# ledControlpcb-NodeMCU.net
KiCad netlist of a schematic drawn in EAGLE
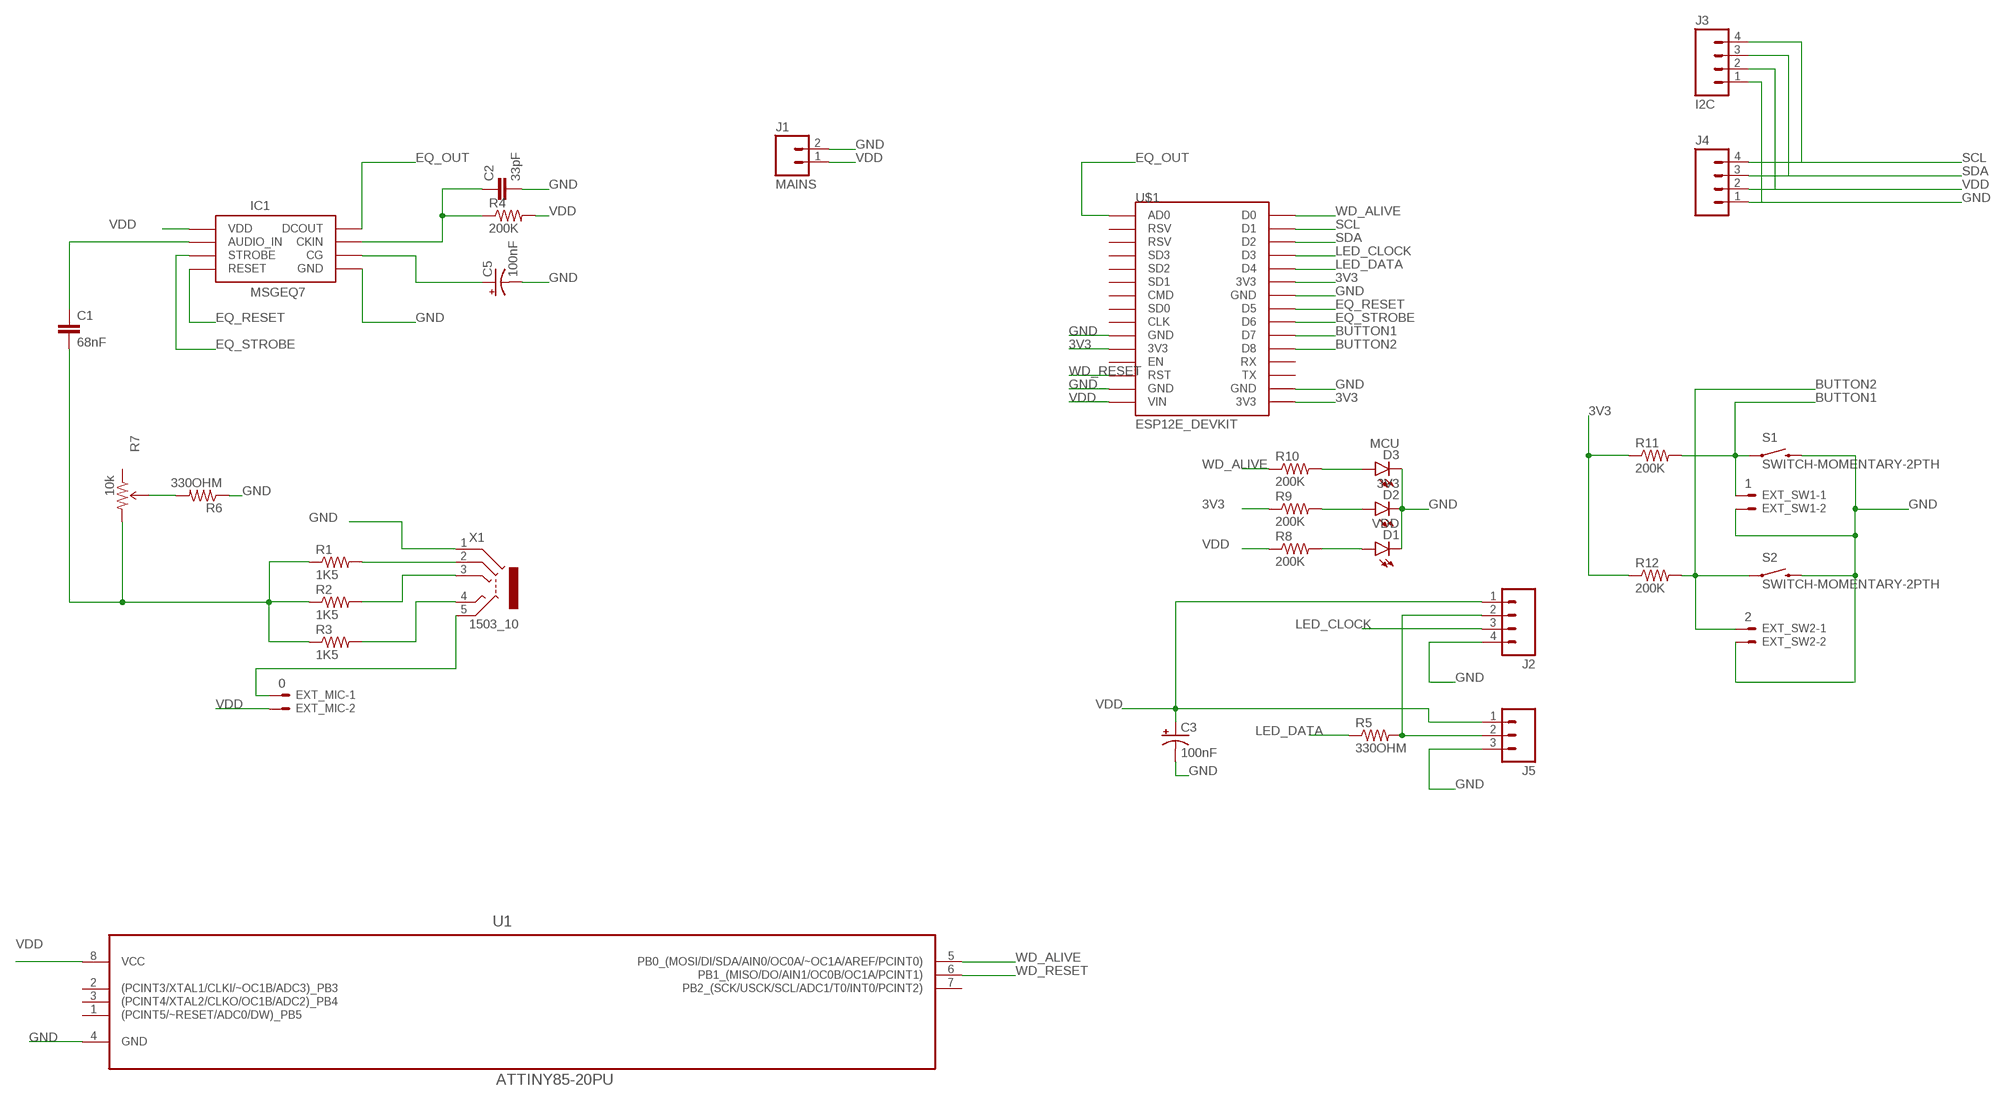
[diagram p0: schematic, sheet 1]

(export (version "E")
  (design (tool "Eeschema 10.0.6"))
  (components
    (comp (ref "C1")
      (value "68nF")
      (footprint "eagle-import:0603-CAP")
      (libsource (lib "eagle-import") (part "CAP0603-CAP"))
    )
    (comp (ref "C2")
      (value "33pF")
      (footprint "eagle-import:0603-CAP")
      (libsource (lib "eagle-import") (part "CAP0603-CAP"))
    )
    (comp (ref "C3")
      (value "100nF")
      (footprint "eagle-import:EIA3216")
      (libsource (lib "eagle-import") (part "CAP_POL1206"))
    )
    (comp (ref "C5")
      (value "100nF")
      (footprint "eagle-import:EIA3216")
      (libsource (lib "eagle-import") (part "CAP_POL1206"))
    )
    (comp (ref "D1")
      (value "VDD")
      (footprint "eagle-import:LED-0603")
      (libsource (lib "eagle-import") (part "LED0603"))
    )
    (comp (ref "D2")
      (value "3V3")
      (footprint "eagle-import:LED-0603")
      (libsource (lib "eagle-import") (part "LED0603"))
    )
    (comp (ref "D3")
      (value "MCU")
      (footprint "eagle-import:LED-0603")
      (libsource (lib "eagle-import") (part "LED0603"))
    )
    (comp (ref "EXT_MIC")
      (value "0")
      (footprint "eagle-import:22-23-2021")
      (fields (field (name "MF") "MOLEX") (field (name "MPN") "22-23-2021"))
      (libsource (lib "eagle-import") (part "22-23-2021"))
    )
    (comp (ref "EXT_SW1")
      (value "1")
      (footprint "eagle-import:22-23-2021")
      (fields (field (name "MF") "MOLEX") (field (name "MPN") "22-23-2021"))
      (libsource (lib "eagle-import") (part "22-23-2021"))
    )
    (comp (ref "EXT_SW2")
      (value "2")
      (footprint "eagle-import:22-23-2021")
      (fields (field (name "MF") "MOLEX") (field (name "MPN") "22-23-2021"))
      (libsource (lib "eagle-import") (part "22-23-2021"))
    )
    (comp (ref "IC1")
      (value "MSGEQ7DIP")
      (footprint "eagle-import:DIL08")
      (libsource (lib "eagle-import") (part "MSGEQ7DIP"))
    )
    (comp (ref "J1")
      (value "MAINS")
      (footprint "eagle-import:JST-2-PTH-VERT")
      (libsource (lib "eagle-import") (part "M02JST-PTH-VERT"))
    )
    (comp (ref "J2")
      (value "M04POLAR")
      (footprint "eagle-import:MOLEX-1X4")
      (libsource (lib "eagle-import") (part "M04POLAR"))
    )
    (comp (ref "J3")
      (value "I2C")
      (footprint "eagle-import:MOLEX-1X4")
      (libsource (lib "eagle-import") (part "M04POLAR"))
    )
    (comp (ref "J4")
      (value "M04POLAR")
      (footprint "eagle-import:MOLEX-1X4")
      (libsource (lib "eagle-import") (part "M04POLAR"))
    )
    (comp (ref "J5")
      (value "M03POLAR")
      (footprint "eagle-import:MOLEX-1X3")
      (libsource (lib "eagle-import") (part "M03POLAR"))
    )
    (comp (ref "R1")
      (value "1K5")
      (footprint "eagle-import:0603-RES")
      (libsource (lib "eagle-import") (part "RESISTOR0603"))
    )
    (comp (ref "R2")
      (value "1K5")
      (footprint "eagle-import:0603-RES")
      (libsource (lib "eagle-import") (part "RESISTOR0603"))
    )
    (comp (ref "R3")
      (value "1K5")
      (footprint "eagle-import:0603-RES")
      (libsource (lib "eagle-import") (part "RESISTOR0603-RES"))
    )
    (comp (ref "R4")
      (value "200K")
      (footprint "eagle-import:0603-RES")
      (libsource (lib "eagle-import") (part "RESISTOR0603"))
    )
    (comp (ref "R5")
      (value "330OHM")
      (footprint "eagle-import:0603-RES")
      (libsource (lib "eagle-import") (part "RESISTOR0603"))
    )
    (comp (ref "R6")
      (value "330OHM")
      (footprint "eagle-import:0603-RES")
      (libsource (lib "eagle-import") (part "RESISTOR0603-RES"))
    )
    (comp (ref "R7")
      (value "10k")
      (footprint "eagle-import:TRIM_POT_PTH")
      (libsource (lib "eagle-import") (part "TRIMPOTPTH"))
    )
    (comp (ref "R8")
      (value "200K")
      (footprint "eagle-import:0603-RES")
      (libsource (lib "eagle-import") (part "RESISTOR0603"))
    )
    (comp (ref "R9")
      (value "200K")
      (footprint "eagle-import:0603-RES")
      (libsource (lib "eagle-import") (part "RESISTOR0603"))
    )
    (comp (ref "R10")
      (value "200K")
      (footprint "eagle-import:0603-RES")
      (libsource (lib "eagle-import") (part "RESISTOR0603"))
    )
    (comp (ref "R11")
      (value "200K")
      (footprint "eagle-import:0603-RES")
      (libsource (lib "eagle-import") (part "RESISTOR0603"))
    )
    (comp (ref "R12")
      (value "200K")
      (footprint "eagle-import:0603-RES")
      (libsource (lib "eagle-import") (part "RESISTOR0603"))
    )
    (comp (ref "S1")
      (value "SWITCH-MOMENTARY-2PTH")
      (footprint "eagle-import:TACTILE-PTH")
      (libsource (lib "eagle-import") (part "SWITCH-MOMENTARY-2PTH"))
    )
    (comp (ref "S2")
      (value "SWITCH-MOMENTARY-2PTH")
      (footprint "eagle-import:TACTILE-PTH")
      (libsource (lib "eagle-import") (part "SWITCH-MOMENTARY-2PTH"))
    )
    (comp (ref "U$1")
      (value "ESP12E_DEVKIT")
      (footprint "eagle-import:ESP12E_DEVKIT")
      (libsource (lib "eagle-import") (part "ESP12E_DEVKIT"))
    )
    (comp (ref "U1")
      (value "ATTINY85-20PU")
      (footprint "eagle-import:DIP254P762X533-8")
      (libsource (lib "eagle-import") (part "ATTINY85-20PU"))
    )
    (comp (ref "X1")
      (value "1503_10")
      (footprint "eagle-import:1503_10")
      (libsource (lib "eagle-import") (part "1503_10"))
    )
  )
  (nets
    (net (code "1") (name "/3V3") (class "Default")
      (node (ref "R11") (pin "1") (pinfunction "1_1") (pintype "passive"))
      (node (ref "R12") (pin "1") (pinfunction "1_1") (pintype "passive"))
      (node (ref "R9") (pin "1") (pinfunction "1_1") (pintype "passive"))
      (node (ref "U$1") (pin "3V3@0") (pinfunction "3V3_3V3@0") (pintype "bidirectional"))
      (node (ref "U$1") (pin "3V3@1") (pinfunction "3V3_3V3@1") (pintype "bidirectional"))
      (node (ref "U$1") (pin "3V3@2") (pinfunction "3V3_3V3@2") (pintype "bidirectional"))
    )
    (net (code "2") (name "/BUTTON1") (class "Default")
      (node (ref "EXT_SW1") (pin "1") (pinfunction "S_1") (pintype "passive"))
      (node (ref "R11") (pin "2") (pinfunction "2_2") (pintype "passive"))
      (node (ref "S1") (pin "1") (pinfunction "1_1") (pintype "passive"))
      (node (ref "U$1") (pin "D7") (pinfunction "D7_D7") (pintype "bidirectional"))
    )
    (net (code "3") (name "/BUTTON2") (class "Default")
      (node (ref "EXT_SW2") (pin "1") (pinfunction "S_1") (pintype "passive"))
      (node (ref "R12") (pin "2") (pinfunction "2_2") (pintype "passive"))
      (node (ref "S2") (pin "1") (pinfunction "1_1") (pintype "passive"))
      (node (ref "U$1") (pin "D8") (pinfunction "D8_D8") (pintype "bidirectional"))
    )
    (net (code "4") (name "/EQ_OUT") (class "Default")
      (node (ref "IC1") (pin "3") (pinfunction "DCOUT_3") (pintype "bidirectional"))
      (node (ref "U$1") (pin "AD0") (pinfunction "AD0_AD0") (pintype "bidirectional"))
    )
    (net (code "5") (name "/EQ_RESET") (class "Default")
      (node (ref "IC1") (pin "7") (pinfunction "RESET_7") (pintype "input"))
      (node (ref "U$1") (pin "D5") (pinfunction "D5_D5") (pintype "bidirectional"))
    )
    (net (code "6") (name "/EQ_STROBE") (class "Default")
      (node (ref "IC1") (pin "4") (pinfunction "STROBE_4") (pintype "input"))
      (node (ref "U$1") (pin "D6") (pinfunction "D6_D6") (pintype "bidirectional"))
    )
    (net (code "7") (name "/GND") (class "Default")
      (node (ref "C2") (pin "2") (pinfunction "2_2") (pintype "passive"))
      (node (ref "C3") (pin "C") (pinfunction "-_C") (pintype "passive"))
      (node (ref "C5") (pin "C") (pinfunction "-_C") (pintype "passive"))
      (node (ref "D1") (pin "C") (pinfunction "C_C") (pintype "passive"))
      (node (ref "D2") (pin "C") (pinfunction "C_C") (pintype "passive"))
      (node (ref "D3") (pin "C") (pinfunction "C_C") (pintype "passive"))
      (node (ref "EXT_SW1") (pin "2") (pinfunction "S_2") (pintype "passive"))
      (node (ref "EXT_SW2") (pin "2") (pinfunction "S_2") (pintype "passive"))
      (node (ref "IC1") (pin "2") (pinfunction "GND_2") (pintype "bidirectional"))
      (node (ref "J1") (pin "2") (pinfunction "2_2") (pintype "passive"))
      (node (ref "J2") (pin "4") (pinfunction "4_4") (pintype "passive"))
      (node (ref "J3") (pin "1") (pinfunction "1_1") (pintype "passive"))
      (node (ref "J4") (pin "1") (pinfunction "1_1") (pintype "passive"))
      (node (ref "J5") (pin "3") (pinfunction "3_3") (pintype "passive"))
      (node (ref "R6") (pin "1") (pinfunction "1_1") (pintype "passive"))
      (node (ref "S1") (pin "3") (pinfunction "2_3") (pintype "passive"))
      (node (ref "S2") (pin "3") (pinfunction "2_3") (pintype "passive"))
      (node (ref "U$1") (pin "GND@0") (pinfunction "GND_GND@0") (pintype "bidirectional"))
      (node (ref "U$1") (pin "GND@1") (pinfunction "GND_GND@1") (pintype "bidirectional"))
      (node (ref "U$1") (pin "GND@2") (pinfunction "GND_GND@2") (pintype "bidirectional"))
      (node (ref "U$1") (pin "GND@3") (pinfunction "GND_GND@3") (pintype "bidirectional"))
      (node (ref "U1") (pin "4") (pinfunction "GND_4") (pintype "passive"))
      (node (ref "X1") (pin "1") (pinfunction "1_1") (pintype "passive"))
    )
    (net (code "8") (name "/LED_CLOCK") (class "Default")
      (node (ref "J2") (pin "3") (pinfunction "3_3") (pintype "passive"))
      (node (ref "U$1") (pin "D3") (pinfunction "D3_D3") (pintype "bidirectional"))
    )
    (net (code "9") (name "/LED_DATA") (class "Default")
      (node (ref "R5") (pin "1") (pinfunction "1_1") (pintype "passive"))
      (node (ref "U$1") (pin "D4") (pinfunction "D4_D4") (pintype "bidirectional"))
    )
    (net (code "10") (name "/SCL") (class "Default")
      (node (ref "J3") (pin "4") (pinfunction "4_4") (pintype "passive"))
      (node (ref "J4") (pin "4") (pinfunction "4_4") (pintype "passive"))
      (node (ref "U$1") (pin "D1") (pinfunction "D1_D1") (pintype "bidirectional"))
    )
    (net (code "11") (name "/SDA") (class "Default")
      (node (ref "J3") (pin "3") (pinfunction "3_3") (pintype "passive"))
      (node (ref "J4") (pin "3") (pinfunction "3_3") (pintype "passive"))
      (node (ref "U$1") (pin "D2") (pinfunction "D2_D2") (pintype "bidirectional"))
    )
    (net (code "12") (name "/VDD") (class "Default")
      (node (ref "C3") (pin "A") (pinfunction "+_A") (pintype "passive"))
      (node (ref "EXT_MIC") (pin "2") (pinfunction "S_2") (pintype "passive"))
      (node (ref "IC1") (pin "1") (pinfunction "VDD_1") (pintype "input"))
      (node (ref "J1") (pin "1") (pinfunction "1_1") (pintype "passive"))
      (node (ref "J2") (pin "1") (pinfunction "1_1") (pintype "passive"))
      (node (ref "J3") (pin "2") (pinfunction "2_2") (pintype "passive"))
      (node (ref "J4") (pin "2") (pinfunction "2_2") (pintype "passive"))
      (node (ref "J5") (pin "1") (pinfunction "1_1") (pintype "passive"))
      (node (ref "R4") (pin "2") (pinfunction "2_2") (pintype "passive"))
      (node (ref "R8") (pin "1") (pinfunction "1_1") (pintype "passive"))
      (node (ref "U$1") (pin "VIN") (pinfunction "VIN_VIN") (pintype "bidirectional"))
      (node (ref "U1") (pin "8") (pinfunction "VCC_8") (pintype "power_in"))
    )
    (net (code "13") (name "/WD_ALIVE") (class "Default")
      (node (ref "R10") (pin "1") (pinfunction "1_1") (pintype "passive"))
      (node (ref "U$1") (pin "D0") (pinfunction "D0_D0") (pintype "bidirectional"))
      (node (ref "U1") (pin "5") (pinfunction "PB0_(MOSI/DI/SDA/AIN0/OC0A/~{OC1A/AREF/PCINT0})_5") (pintype "bidirectional"))
    )
    (net (code "14") (name "/WD_RESET") (class "Default")
      (node (ref "U$1") (pin "RST") (pinfunction "RST_RST") (pintype "bidirectional"))
      (node (ref "U1") (pin "6") (pinfunction "PB1_(MISO/DO/AIN1/OC0B/OC1A/PCINT1)_6") (pintype "bidirectional"))
    )
    (net (code "15") (name "Net-(C5-+)") (class "Default")
      (node (ref "C5") (pin "A") (pinfunction "+_A") (pintype "passive"))
      (node (ref "IC1") (pin "6") (pinfunction "CG_6") (pintype "bidirectional"))
    )
    (net (code "16") (name "Net-(D1-PadA)") (class "Default")
      (node (ref "D1") (pin "A") (pinfunction "A_A") (pintype "passive"))
      (node (ref "R8") (pin "2") (pinfunction "2_2") (pintype "passive"))
    )
    (net (code "17") (name "Net-(D2-PadA)") (class "Default")
      (node (ref "D2") (pin "A") (pinfunction "A_A") (pintype "passive"))
      (node (ref "R9") (pin "2") (pinfunction "2_2") (pintype "passive"))
    )
    (net (code "18") (name "Net-(D3-PadA)") (class "Default")
      (node (ref "D3") (pin "A") (pinfunction "A_A") (pintype "passive"))
      (node (ref "R10") (pin "2") (pinfunction "2_2") (pintype "passive"))
    )
    (net (code "19") (name "Net-(EXT_MICA-S)") (class "Default")
      (node (ref "EXT_MIC") (pin "1") (pinfunction "S_1") (pintype "passive"))
      (node (ref "X1") (pin "5") (pinfunction "5_5") (pintype "passive"))
    )
    (net (code "20") (name "Net-(IC1-AUDIO_IN)") (class "Default")
      (node (ref "C1") (pin "1") (pinfunction "1_1") (pintype "passive"))
      (node (ref "IC1") (pin "5") (pinfunction "AUDIO_IN_5") (pintype "input"))
    )
    (net (code "21") (name "Net-(IC1-CKIN)") (class "Default")
      (node (ref "C2") (pin "1") (pinfunction "1_1") (pintype "passive"))
      (node (ref "IC1") (pin "8") (pinfunction "CKIN_8") (pintype "bidirectional"))
      (node (ref "R4") (pin "1") (pinfunction "1_1") (pintype "passive"))
    )
    (net (code "22") (name "Net-(J2-Pad2)") (class "Default")
      (node (ref "J2") (pin "2") (pinfunction "2_2") (pintype "passive"))
      (node (ref "J5") (pin "2") (pinfunction "2_2") (pintype "passive"))
      (node (ref "R5") (pin "2") (pinfunction "2_2") (pintype "passive"))
    )
    (net (code "23") (name "Net-(R1-Pad2)") (class "Default")
      (node (ref "R1") (pin "2") (pinfunction "2_2") (pintype "passive"))
      (node (ref "X1") (pin "2") (pinfunction "2_2") (pintype "passive"))
    )
    (net (code "24") (name "Net-(R2-Pad2)") (class "Default")
      (node (ref "R2") (pin "2") (pinfunction "2_2") (pintype "passive"))
      (node (ref "X1") (pin "3") (pinfunction "3_3") (pintype "passive"))
    )
    (net (code "25") (name "Net-(R3-Pad2)") (class "Default")
      (node (ref "R3") (pin "2") (pinfunction "2_2") (pintype "passive"))
      (node (ref "X1") (pin "4") (pinfunction "4_4") (pintype "passive"))
    )
    (net (code "26") (name "Net-(R7-CW)") (class "Default")
      (node (ref "C1") (pin "2") (pinfunction "2_2") (pintype "passive"))
      (node (ref "R1") (pin "1") (pinfunction "1_1") (pintype "passive"))
      (node (ref "R2") (pin "1") (pinfunction "1_1") (pintype "passive"))
      (node (ref "R3") (pin "1") (pinfunction "1_1") (pintype "passive"))
      (node (ref "R7") (pin "3") (pinfunction "CW_3") (pintype "passive"))
    )
    (net (code "27") (name "Net-(R7-WIPER)") (class "Default")
      (node (ref "R6") (pin "2") (pinfunction "2_2") (pintype "passive"))
      (node (ref "R7") (pin "2") (pinfunction "WIPER_2") (pintype "passive"))
    )
    (net (code "28") (name "unconnected-(R7-CCW-Pad1)") (class "Default")
      (node (ref "R7") (pin "1") (pinfunction "CCW_1") (pintype "passive"))
    )
    (net (code "29") (name "unconnected-(U$1-PadCLK)") (class "Default")
      (node (ref "U$1") (pin "CLK") (pinfunction "CLK_CLK") (pintype "bidirectional"))
    )
    (net (code "30") (name "unconnected-(U$1-PadCMD)") (class "Default")
      (node (ref "U$1") (pin "CMD") (pinfunction "CMD_CMD") (pintype "bidirectional"))
    )
    (net (code "31") (name "unconnected-(U$1-PadEN)") (class "Default")
      (node (ref "U$1") (pin "EN") (pinfunction "EN_EN") (pintype "bidirectional"))
    )
    (net (code "32") (name "unconnected-(U$1-PadRX)") (class "Default")
      (node (ref "U$1") (pin "RX") (pinfunction "RX_RX") (pintype "bidirectional"))
    )
    (net (code "33") (name "unconnected-(U$1-PadSD0)") (class "Default")
      (node (ref "U$1") (pin "SD0") (pinfunction "SD0_SD0") (pintype "bidirectional"))
    )
    (net (code "34") (name "unconnected-(U$1-PadSD1)") (class "Default")
      (node (ref "U$1") (pin "SD1") (pinfunction "SD1_SD1") (pintype "bidirectional"))
    )
    (net (code "35") (name "unconnected-(U$1-PadSD2)") (class "Default")
      (node (ref "U$1") (pin "SD2") (pinfunction "SD2_SD2") (pintype "bidirectional"))
    )
    (net (code "36") (name "unconnected-(U$1-PadSD3)") (class "Default")
      (node (ref "U$1") (pin "SD3") (pinfunction "SD3_SD3") (pintype "bidirectional"))
    )
    (net (code "37") (name "unconnected-(U$1-PadTX)") (class "Default")
      (node (ref "U$1") (pin "TX") (pinfunction "TX_TX") (pintype "bidirectional"))
    )
    (net (code "38") (name "unconnected-(U$1-RSV-PadRSV@0)") (class "Default")
      (node (ref "U$1") (pin "RSV@0") (pinfunction "RSV_RSV@0") (pintype "bidirectional"))
    )
    (net (code "39") (name "unconnected-(U$1-RSV-PadRSV@1)") (class "Default")
      (node (ref "U$1") (pin "RSV@1") (pinfunction "RSV_RSV@1") (pintype "bidirectional"))
    )
    (net (code "40") (name "unconnected-(U1-(PCINT3{slash}XTAL1{slash}CLKI{slash}~{OC1B{slash}ADC3})_PB3-Pad2)") (class "Default")
      (node (ref "U1") (pin "2") (pinfunction "(PCINT3/XTAL1/CLKI/~{OC1B/ADC3})_PB3_2") (pintype "bidirectional"))
    )
    (net (code "41") (name "unconnected-(U1-(PCINT4{slash}XTAL2{slash}CLKO{slash}OC1B{slash}ADC2)_PB4-Pad3)") (class "Default")
      (node (ref "U1") (pin "3") (pinfunction "(PCINT4/XTAL2/CLKO/OC1B/ADC2)_PB4_3") (pintype "bidirectional"))
    )
    (net (code "42") (name "unconnected-(U1-(PCINT5{slash}~{RESET{slash}ADC0{slash}DW})_PB5-Pad1)") (class "Default")
      (node (ref "U1") (pin "1") (pinfunction "(PCINT5/~{RESET/ADC0/DW})_PB5_1") (pintype "bidirectional"))
    )
    (net (code "43") (name "unconnected-(U1-PB2_(SCK{slash}USCK{slash}SCL{slash}ADC1{slash}T0{slash}INT0{slash}PCINT2)-Pad7)") (class "Default")
      (node (ref "U1") (pin "7") (pinfunction "PB2_(SCK/USCK/SCL/ADC1/T0/INT0/PCINT2)_7") (pintype "bidirectional"))
    )
  )
)
